# 04_Sensor.net
KiCad netlist of a schematic drawn in Altium Designer
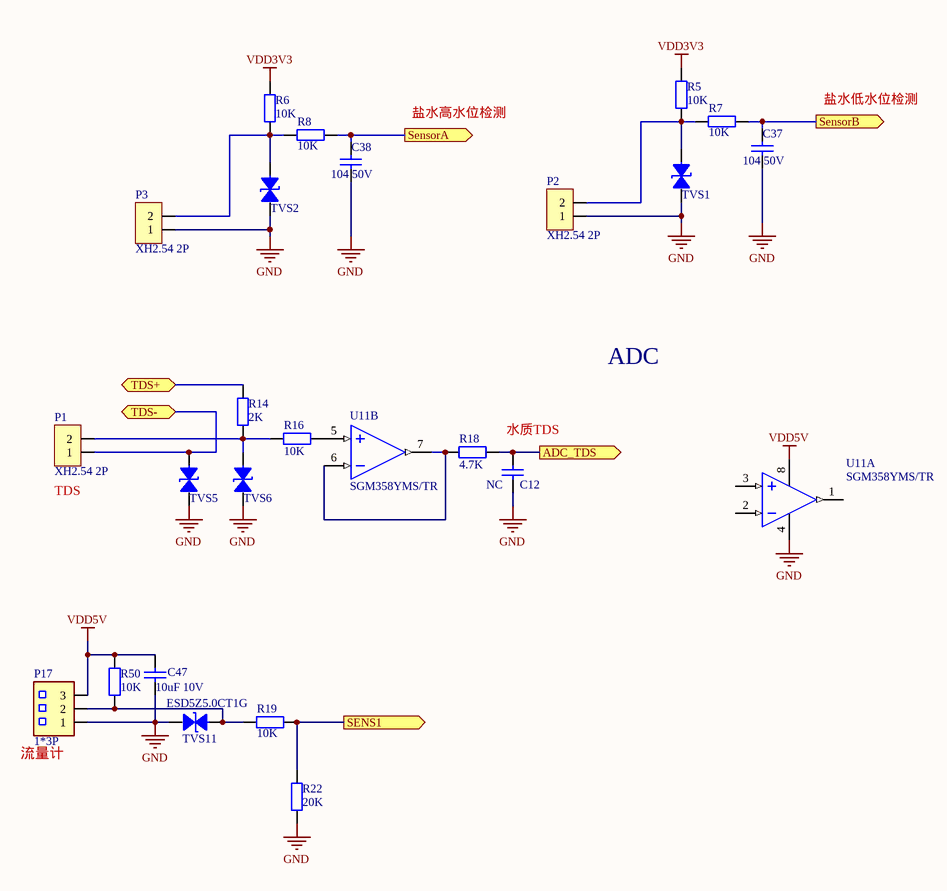
[diagram p0: 04_Sensor.SchDoc]

(export (version "E")
  (design (tool "Eeschema 10.0.6"))
  (components
    (comp (ref "C12")
      (value "NC")
      (footprint "SMD-0603C")
      (description "贴片电容 10%")
      (libsource (lib "XiaoyI") (part "CAP4"))
    )
    (comp (ref "C37")
      (value "104 50V")
      (footprint "SMD-0603C")
      (description "贴片电容 20%")
      (libsource (lib "XiaoyI") (part "CAP4"))
    )
    (comp (ref "C38")
      (value "104 50V")
      (footprint "SMD-0603C")
      (description "贴片电容 20%")
      (libsource (lib "XiaoyI") (part "CAP4"))
    )
    (comp (ref "C47")
      (value "10uF 10V")
      (footprint "SMD-0603C")
      (description "贴片电容 10%")
      (libsource (lib "Miscellaneous Devices LC") (part "0805 22uF (226) 20% 25V"))
    )
    (comp (ref "P1")
      (value "XH2.54 2P")
      (footprint "SIP-2A")
      (description "XH2.54 2P 直插")
      (libsource (lib "XiaoyI") (part "SIP-2"))
    )
    (comp (ref "P2")
      (value "XH2.54 2P")
      (footprint "SIP-2A")
      (description "XH2.54 2P 直插")
      (libsource (lib "XiaoyI") (part "SIP-2"))
    )
    (comp (ref "P3")
      (value "XH2.54 2P")
      (footprint "SIP-2A")
      (description "XH2.54 2P 直插")
      (libsource (lib "XiaoyI") (part "SIP-2"))
    )
    (comp (ref "P17")
      (value "1*3P")
      (footprint "3X2.54MMZ2")
      (libsource (lib "PARK-N5 V1.0") (part "HDR1*3"))
    )
    (comp (ref "R5")
      (value "10K")
      (footprint "SMD-0603")
      (description "贴片电阻 1%")
      (libsource (lib "ABB") (part "RES0"))
    )
    (comp (ref "R6")
      (value "10K")
      (footprint "SMD-0603")
      (description "贴片电阻 1%")
      (libsource (lib "ABB") (part "RES0"))
    )
    (comp (ref "R7")
      (value "10K")
      (footprint "SMD-0603")
      (description "贴片电阻 1%")
      (libsource (lib "") (part "RES0_1"))
    )
    (comp (ref "R8")
      (value "10K")
      (footprint "SMD-0603")
      (description "贴片电阻 1%")
      (libsource (lib "") (part "RES0_1"))
    )
    (comp (ref "R14")
      (value "2K")
      (footprint "SMD-0603")
      (description "贴片电阻 1%")
      (libsource (lib "ABB") (part "RES0"))
    )
    (comp (ref "R16")
      (value "10K")
      (footprint "SMD-0603")
      (description "贴片电阻 1%")
      (libsource (lib "") (part "RES0_1"))
    )
    (comp (ref "R18")
      (value "4.7K")
      (footprint "SMD-0603")
      (description "贴片电阻 5%")
      (libsource (lib "") (part "RES0_2"))
    )
    (comp (ref "R19")
      (value "10K")
      (footprint "SMD-0603")
      (description "贴片电阻 5%")
      (libsource (lib "Miscellaneous Devices LC") (part "0603 10KΩ (1002) 1%"))
    )
    (comp (ref "R22")
      (value "20K")
      (footprint "SMD-0603")
      (description "贴片电阻 5%")
      (libsource (lib "") (part "0603 10KΩ (1002) 1%_1"))
    )
    (comp (ref "R50")
      (value "10K")
      (footprint "SMD-0603")
      (description "贴片电阻 5%")
      (libsource (lib "") (part "0603 10KΩ (1002) 1%_2"))
    )
    (comp (ref "TVS1")
      (value "ESD5Z5.0CT1G")
      (footprint "SOD-523")
      (description "TVS")
      (libsource (lib "XiaoyI") (part "TVS-1"))
    )
    (comp (ref "TVS2")
      (value "ESD5Z5.0CT1G")
      (footprint "SOD-523")
      (description "TVS")
      (libsource (lib "XiaoyI") (part "TVS-1"))
    )
    (comp (ref "TVS5")
      (value "ESD5Z5.0CT1G")
      (footprint "SOD-523")
      (description "TVS")
      (libsource (lib "XiaoyI") (part "TVS-1"))
    )
    (comp (ref "TVS6")
      (value "ESD5Z5.0CT1G")
      (footprint "SOD-523")
      (description "TVS")
      (libsource (lib "XiaoyI") (part "TVS-1"))
    )
    (comp (ref "TVS11")
      (value "ESD5Z5.0CT1G")
      (footprint "SOD-523")
      (description "TVS 5.0V")
      (libsource (lib "XiaoyI") (part "TVS-1"))
    )
    (comp (ref "U11")
      (value "SGM358YMS/TR")
      (footprint "MSOP-8")
      (description "运放")
      (libsource (lib "XiaoyI") (part "LM358"))
    )
  )
  (nets
    (net (code "1") (name "/ADC_TDS") (class "Default")
      (node (ref "C12") (pin "2") (pinfunction "2_2") (pintype "passive"))
      (node (ref "R18") (pin "1") (pinfunction "1_1") (pintype "passive"))
    )
    (net (code "2") (name "/SENS1") (class "Default")
      (node (ref "R19") (pin "2") (pinfunction "2_2") (pintype "passive"))
      (node (ref "R22") (pin "2") (pinfunction "2_2") (pintype "passive"))
    )
    (net (code "3") (name "/SensorA") (class "Default")
      (node (ref "C38") (pin "2") (pinfunction "2_2") (pintype "passive"))
      (node (ref "R8") (pin "2") (pinfunction "2_2") (pintype "passive"))
    )
    (net (code "4") (name "/SensorB") (class "Default")
      (node (ref "C37") (pin "2") (pinfunction "2_2") (pintype "passive"))
      (node (ref "R7") (pin "2") (pinfunction "2_2") (pintype "passive"))
    )
    (net (code "5") (name "/TDS+") (class "Default")
      (node (ref "R14") (pin "1") (pinfunction "1_1") (pintype "passive"))
    )
    (net (code "6") (name "/TDS-") (class "Default")
      (node (ref "P1") (pin "1") (pinfunction "1_1") (pintype "passive"))
      (node (ref "TVS5") (pin "2") (pinfunction "B_2") (pintype "passive"))
    )
    (net (code "7") (name "GND") (class "Default")
      (node (ref "C12") (pin "1") (pinfunction "1_1") (pintype "passive"))
      (node (ref "C37") (pin "1") (pinfunction "1_1") (pintype "passive"))
      (node (ref "C38") (pin "1") (pinfunction "1_1") (pintype "passive"))
      (node (ref "C47") (pin "1") (pinfunction "1_1") (pintype "passive"))
      (node (ref "P17") (pin "1") (pinfunction "1_1") (pintype "passive"))
      (node (ref "P2") (pin "1") (pinfunction "1_1") (pintype "passive"))
      (node (ref "P3") (pin "1") (pinfunction "1_1") (pintype "passive"))
      (node (ref "R22") (pin "1") (pinfunction "1_1") (pintype "passive"))
      (node (ref "TVS1") (pin "1") (pinfunction "A_1") (pintype "passive"))
      (node (ref "TVS11") (pin "1") (pinfunction "A_1") (pintype "passive"))
      (node (ref "TVS2") (pin "1") (pinfunction "A_1") (pintype "passive"))
      (node (ref "TVS5") (pin "1") (pinfunction "A_1") (pintype "passive"))
      (node (ref "TVS6") (pin "1") (pinfunction "A_1") (pintype "passive"))
      (node (ref "U11") (pin "4") (pinfunction "V-_4") (pintype "power_in"))
    )
    (net (code "8") (name "Net-(TVS1-B)") (class "Default")
      (node (ref "P2") (pin "2") (pinfunction "2_2") (pintype "passive"))
      (node (ref "R5") (pin "2") (pinfunction "2_2") (pintype "passive"))
      (node (ref "R7") (pin "1") (pinfunction "1_1") (pintype "passive"))
      (node (ref "TVS1") (pin "2") (pinfunction "B_2") (pintype "passive"))
    )
    (net (code "9") (name "Net-(TVS2-B)") (class "Default")
      (node (ref "P3") (pin "2") (pinfunction "2_2") (pintype "passive"))
      (node (ref "R6") (pin "2") (pinfunction "2_2") (pintype "passive"))
      (node (ref "R8") (pin "1") (pinfunction "1_1") (pintype "passive"))
      (node (ref "TVS2") (pin "2") (pinfunction "B_2") (pintype "passive"))
    )
    (net (code "10") (name "Net-(TVS6-B)") (class "Default")
      (node (ref "P1") (pin "2") (pinfunction "2_2") (pintype "passive"))
      (node (ref "R14") (pin "2") (pinfunction "2_2") (pintype "passive"))
      (node (ref "R16") (pin "1") (pinfunction "1_1") (pintype "passive"))
      (node (ref "TVS6") (pin "2") (pinfunction "B_2") (pintype "passive"))
    )
    (net (code "11") (name "Net-(TVS11-B)") (class "Default")
      (node (ref "P17") (pin "2") (pinfunction "2_2") (pintype "passive"))
      (node (ref "R19") (pin "1") (pinfunction "1_1") (pintype "passive"))
      (node (ref "R50") (pin "2") (pinfunction "2_2") (pintype "passive"))
      (node (ref "TVS11") (pin "2") (pinfunction "B_2") (pintype "passive"))
    )
    (net (code "12") (name "Net-(U11B-IN2+)") (class "Default")
      (node (ref "R16") (pin "2") (pinfunction "2_2") (pintype "passive"))
      (node (ref "U11") (pin "5") (pinfunction "IN2+_5") (pintype "input"))
    )
    (net (code "13") (name "Net-(U11B-IN2-)") (class "Default")
      (node (ref "R18") (pin "2") (pinfunction "2_2") (pintype "passive"))
      (node (ref "U11") (pin "6") (pinfunction "IN2-_6") (pintype "input"))
      (node (ref "U11") (pin "7") (pinfunction "OUT2_7") (pintype "output"))
    )
    (net (code "14") (name "VDD3V3") (class "Default")
      (node (ref "R5") (pin "1") (pinfunction "1_1") (pintype "passive"))
      (node (ref "R6") (pin "1") (pinfunction "1_1") (pintype "passive"))
    )
    (net (code "15") (name "VDD5V") (class "Default")
      (node (ref "C47") (pin "2") (pinfunction "2_2") (pintype "passive"))
      (node (ref "P17") (pin "3") (pinfunction "3_3") (pintype "passive"))
      (node (ref "R50") (pin "1") (pinfunction "1_1") (pintype "passive"))
      (node (ref "U11") (pin "8") (pinfunction "V+_8") (pintype "power_in"))
    )
    (net (code "16") (name "unconnected-(U11A-IN1+-Pad3)") (class "Default")
      (node (ref "U11") (pin "3") (pinfunction "IN1+_3") (pintype "input"))
    )
    (net (code "17") (name "unconnected-(U11A-IN1--Pad2)") (class "Default")
      (node (ref "U11") (pin "2") (pinfunction "IN1-_2") (pintype "input"))
    )
    (net (code "18") (name "unconnected-(U11A-OUT1-Pad1)") (class "Default")
      (node (ref "U11") (pin "1") (pinfunction "OUT1_1") (pintype "output"))
    )
  )
)
